# DMX.net
KiCad netlist of a schematic drawn in Altium Designer
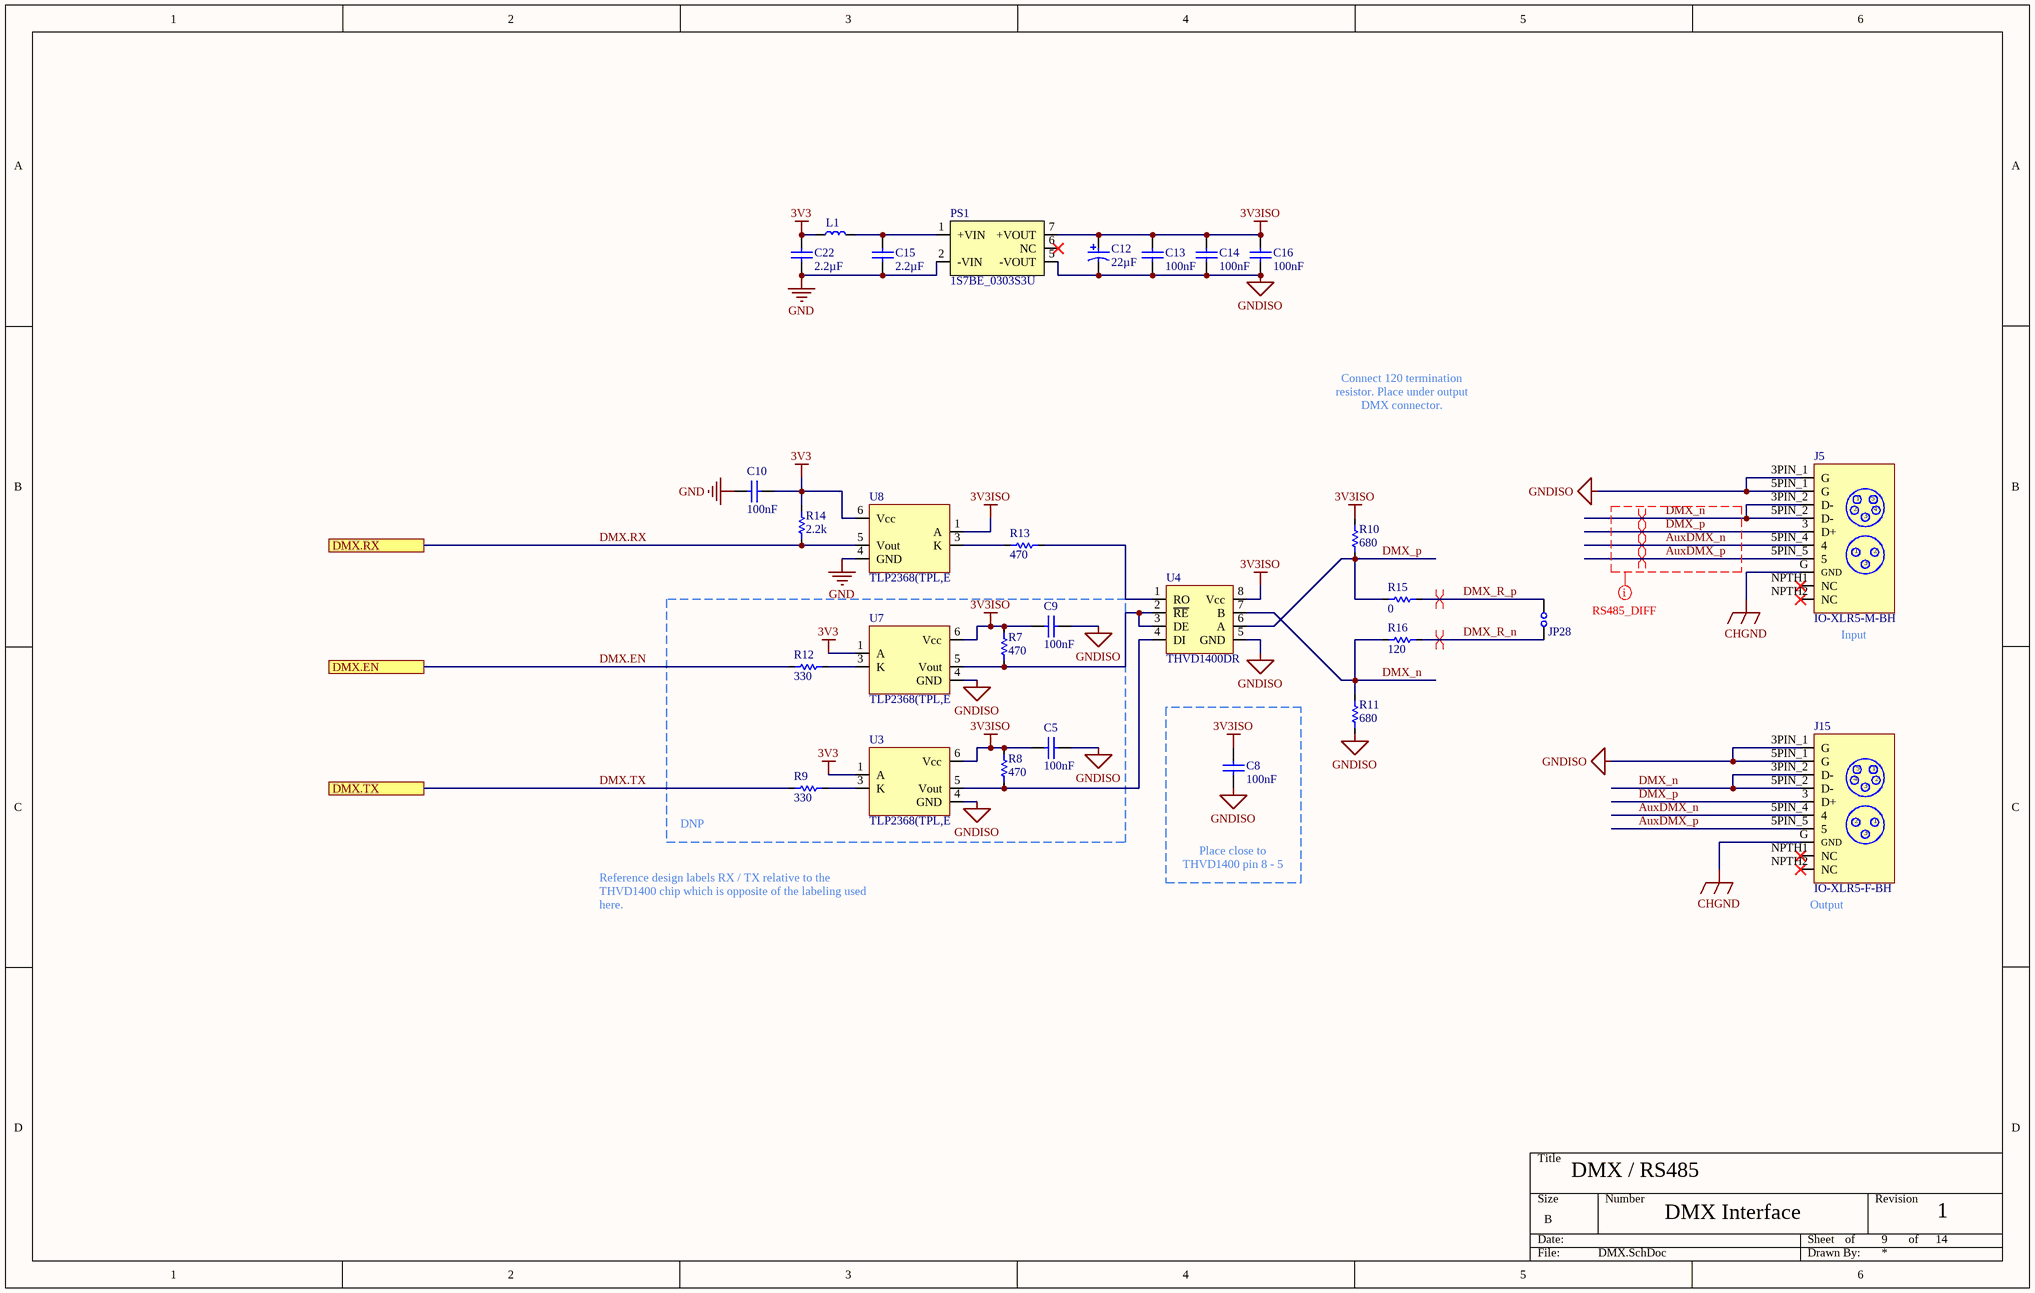
[diagram p0: DMX.SchDoc]

(export (version "E")
  (design (tool "Eeschema 10.0.6"))
  (components
    (comp (ref "C5")
      (value "100nF")
      (footprint "CAPC1608X10N_0603_MED")
      (fields (field (name "Comment") "CC0603KRX7R0BB104"))
      (libsource (lib "Equus Computer Systems") (part "CAP-NP-2"))
    )
    (comp (ref "C8")
      (value "100nF")
      (footprint "CAPC1608X10N_0603_MED")
      (fields (field (name "Comment") "CC0603KRX7R0BB104"))
      (libsource (lib "Equus Computer Systems") (part "CAP-NP-2"))
    )
    (comp (ref "C9")
      (value "100nF")
      (footprint "CAPC1608X10N_0603_MED")
      (fields (field (name "Comment") "CC0603KRX7R0BB104"))
      (libsource (lib "Equus Computer Systems") (part "CAP-NP-2"))
    )
    (comp (ref "C10")
      (value "100nF")
      (footprint "CAPC1608X10N_0603_MED")
      (fields (field (name "Comment") "CC0603KRX7R0BB104"))
      (libsource (lib "Equus Computer Systems") (part "CAP-NP-2"))
    )
    (comp (ref "C12")
      (value "22µF")
      (footprint "CAPCP3528X21N_1210_1411_MED")
      (fields (field (name "TOLERANCE") "10%") (field (name "Comment") "TPSB226K010R0500"))
      (libsource (lib "Equus Computer Systems") (part "CAP-P-2"))
    )
    (comp (ref "C13")
      (value "100nF")
      (footprint "CAPC1608X10N_0603_MED")
      (fields (field (name "Comment") "CC0603KRX7R0BB104"))
      (libsource (lib "Equus Computer Systems") (part "CAP-NP-2"))
    )
    (comp (ref "C14")
      (value "100nF")
      (footprint "CAPC1608X10N_0603_MED")
      (fields (field (name "Comment") "CC0603KRX7R0BB104"))
      (libsource (lib "Equus Computer Systems") (part "CAP-NP-2"))
    )
    (comp (ref "C15")
      (value "2.2µF")
      (footprint "CAPC2012X14N_0805_MED")
      (description "Ceramic Capacitor, Multilayer, Ceramic, 2.2uF, 50V, 10%, X6S, 0805")
      (fields (field (name "TOLERANCE") "10%") (field (name "Comment") "CGA4J3X7R1H225K125AE"))
      (libsource (lib "Equus Computer Systems") (part "CAP-NP-2"))
    )
    (comp (ref "C16")
      (value "100nF")
      (footprint "CAPC1608X10N_0603_MED")
      (fields (field (name "Comment") "CC0603KRX7R0BB104"))
      (libsource (lib "Equus Computer Systems") (part "CAP-NP-2"))
    )
    (comp (ref "C22")
      (value "2.2µF")
      (footprint "CAPC2012X14N_0805_MED")
      (description "Ceramic Capacitor, Multilayer, Ceramic, 2.2uF, 50V, 10%, X6S, 0805")
      (fields (field (name "TOLERANCE") "10%") (field (name "Comment") "CGA4J3X7R1H225K125AE"))
      (libsource (lib "Equus Computer Systems") (part "CAP-NP-2"))
    )
    (comp (ref "J5")
      (value "IO-XLR5-M-BH")
      (footprint "IO-XLR5-M-BH-Footprint-1")
      (description "B Series, 5 Pin XLR, Male, Horizontal Pcb Mount With Separate Ground Pin")
      (libsource (lib "Equus Computer Systems") (part "XLR5-M"))
    )
    (comp (ref "J15")
      (value "IO-XLR5-F-BH")
      (footprint "IO-XLR5-F-BH-Footprint-1")
      (description "B-Series 5-Pin XLR Female Horizontal PCB Mount with Separate Ground-Pin Metal Face Plate")
      (libsource (lib "Equus Computer Systems") (part "XLR5-F"))
    )
    (comp (ref "JP28")
      (value "Jumper 2 x 1 NO 0.1\" SMT")
      (footprint "Jumper 2 x 1 NO 0.1\" SMT-Footprint-1")
      (libsource (lib "Equus Computer Systems") (part "Jumper 2 NO"))
    )
    (comp (ref "L1")
      (value "SRR6038-180Y")
      (footprint "IND_SRR6038-180Y")
      (description "General Purpose Inductor, 18uH, 30%, 1 Element, Ferrite-Core, SMD, 2727")
      (fields (field (name "TOLERANCE") "30%"))
      (libsource (lib "Equus Computer Systems") (part "IND-2"))
    )
    (comp (ref "PS1")
      (value "1S7BE_0303S3U")
      (footprint "CONV_1S7BE_0303S3U")
      (description "ISOLATED MODULE DC DC CONVERTERS")
      (fields (field (name "MF") "Gaptec"))
      (libsource (lib "Equus Computer Systems") (part "1S7BE_0303S3U"))
    )
    (comp (ref "R7")
      (value "470")
      (footprint "RESC1608X06N_0603_MED")
      (fields
        (field (name "TOLERANCE") "1%")
        (field (name "POWER") "100mW")
        (field (name "Comment") "RC0603FR-07470RL")
      )
      (libsource (lib "Equus Computer Systems") (part "RES-2"))
    )
    (comp (ref "R8")
      (value "470")
      (footprint "RESC1608X06N_0603_MED")
      (fields
        (field (name "TOLERANCE") "1%")
        (field (name "POWER") "100mW")
        (field (name "Comment") "RC0603FR-07470RL")
      )
      (libsource (lib "Equus Computer Systems") (part "RES-2"))
    )
    (comp (ref "R9")
      (value "330")
      (footprint "RESC1608X06N_0603_MED")
      (fields
        (field (name "POWER") "100mW")
        (field (name "TOLERANCE") "1%")
        (field (name "Comment") "RC0603FR-07330RL")
      )
      (libsource (lib "Equus Computer Systems") (part "RES-2"))
    )
    (comp (ref "R10")
      (value "680")
      (footprint "RESC1608X06N_0603_MED")
      (fields
        (field (name "TOLERANCE") "1%")
        (field (name "POWER") "100mW")
        (field (name "Comment") "RC0603FR-07680RL")
      )
      (libsource (lib "Equus Computer Systems") (part "RES-2"))
    )
    (comp (ref "R11")
      (value "680")
      (footprint "RESC1608X06N_0603_MED")
      (fields
        (field (name "TOLERANCE") "1%")
        (field (name "POWER") "100mW")
        (field (name "Comment") "RC0603FR-07680RL")
      )
      (libsource (lib "Equus Computer Systems") (part "RES-2"))
    )
    (comp (ref "R12")
      (value "330")
      (footprint "RESC1608X06N_0603_MED")
      (fields
        (field (name "POWER") "100mW")
        (field (name "TOLERANCE") "1%")
        (field (name "Comment") "RC0603FR-07330RL")
      )
      (libsource (lib "Equus Computer Systems") (part "RES-2"))
    )
    (comp (ref "R13")
      (value "470")
      (footprint "RESC1608X06N_0603_MED")
      (fields
        (field (name "TOLERANCE") "1%")
        (field (name "POWER") "100mW")
        (field (name "Comment") "RC0603FR-07470RL")
      )
      (libsource (lib "Equus Computer Systems") (part "RES-2"))
    )
    (comp (ref "R14")
      (value "2.2k")
      (footprint "RESC1608X06N_0603_MED")
      (fields
        (field (name "TOLERANCE") "1%")
        (field (name "POWER") "100mW")
        (field (name "Comment") "RC0603FR-072K2L")
      )
      (libsource (lib "Equus Computer Systems") (part "RES-2"))
    )
    (comp (ref "R15")
      (value "0")
      (footprint "RESC1608X06N_0603_MED")
      (description "RC Series 0603 0.1 W 0 Ohm Jumper Surface Mount Thick Film Chip Resistor")
      (fields (field (name "POWER") "100mW") (field (name "TOLERANCE") "1%"))
      (libsource (lib "Equus Computer Systems") (part "RES-2"))
    )
    (comp (ref "R16")
      (value "120")
      (footprint "RESC1608X06N_0603_MED")
      (description "Res General Purpose Thick Film 0603 120 Ohm 1% 1/10W ±100ppm/°C Molded SMD Paper T/R")
      (fields (field (name "POWER") "100mW") (field (name "TOLERANCE") "1%"))
      (libsource (lib "Equus Computer Systems") (part "RES-2"))
    )
    (comp (ref "U3")
      (value "TLP2368(TPL,E")
      (footprint "SOT125P700X220-5N")
      (description "Logic IC Output Optocoupler, 1-Channel, 1-Element, 3750V Isolation, 20MBps")
      (libsource (lib "Equus Computer Systems") (part "TLP2368-Symbol-1"))
    )
    (comp (ref "U4")
      (value "THVD1400DR")
      (footprint "SOIC127P600X175-8N")
      (description "Line Transceiver, 1 Func, 1 Driver, 1 Rcvr, PDSO8")
      (libsource (lib "Equus Computer Systems") (part "THVD1400DR"))
    )
    (comp (ref "U7")
      (value "TLP2368(TPL,E")
      (footprint "SOT125P700X220-5N")
      (description "Logic IC Output Optocoupler, 1-Channel, 1-Element, 3750V Isolation, 20MBps")
      (libsource (lib "Equus Computer Systems") (part "TLP2368-Symbol-1"))
    )
    (comp (ref "U8")
      (value "TLP2368(TPL,E")
      (footprint "SOT125P700X220-5N")
      (description "Logic IC Output Optocoupler, 1-Channel, 1-Element, 3750V Isolation, 20MBps")
      (libsource (lib "") (part "TLP2368-Symbol-1_1"))
    )
  )
  (nets
    (net (code "1") (name "/AuxDMX_n") (class "Default")
      (node (ref "J15") (pin "5PIN_4") (pinfunction "4_5PIN_4") (pintype "passive"))
      (node (ref "J5") (pin "5PIN_4") (pinfunction "4_5PIN_4") (pintype "passive"))
    )
    (net (code "2") (name "/AuxDMX_p") (class "Default")
      (node (ref "J15") (pin "5PIN_5") (pinfunction "5_5PIN_5") (pintype "passive"))
      (node (ref "J5") (pin "5PIN_5") (pinfunction "5_5PIN_5") (pintype "passive"))
    )
    (net (code "3") (name "/DMX.EN") (class "Default")
      (node (ref "R12") (pin "1") (pinfunction "1_1") (pintype "passive"))
    )
    (net (code "4") (name "/DMX.RX") (class "Default")
      (node (ref "R14") (pin "1") (pinfunction "1_1") (pintype "passive"))
      (node (ref "U8") (pin "5") (pinfunction "Vout_5") (pintype "passive"))
    )
    (net (code "5") (name "/DMX.TX") (class "Default")
      (node (ref "R9") (pin "1") (pinfunction "1_1") (pintype "passive"))
    )
    (net (code "6") (name "/DMX_R_n") (class "Default")
      (node (ref "JP28") (pin "2") (pinfunction "2_2") (pintype "passive"))
      (node (ref "R16") (pin "2") (pinfunction "2_2") (pintype "passive"))
    )
    (net (code "7") (name "/DMX_R_p") (class "Default")
      (node (ref "JP28") (pin "1") (pinfunction "1_1") (pintype "passive"))
      (node (ref "R15") (pin "2") (pinfunction "2_2") (pintype "passive"))
    )
    (net (code "8") (name "/DMX_n") (class "Default")
      (node (ref "J15") (pin "3PIN_2") (pinfunction "D-_3PIN_2") (pintype "passive"))
      (node (ref "J15") (pin "5PIN_2") (pinfunction "D-_5PIN_2") (pintype "passive"))
      (node (ref "J5") (pin "3PIN_2") (pinfunction "D-_3PIN_2") (pintype "passive"))
      (node (ref "J5") (pin "5PIN_2") (pinfunction "D-_5PIN_2") (pintype "passive"))
      (node (ref "R11") (pin "2") (pinfunction "2_2") (pintype "passive"))
      (node (ref "R16") (pin "1") (pinfunction "1_1") (pintype "passive"))
      (node (ref "U4") (pin "7") (pinfunction "B_7") (pintype "passive"))
    )
    (net (code "9") (name "/DMX_p") (class "Default")
      (node (ref "J15") (pin "3") (pinfunction "D+_3") (pintype "passive"))
      (node (ref "J5") (pin "3") (pinfunction "D+_3") (pintype "passive"))
      (node (ref "R10") (pin "1") (pinfunction "1_1") (pintype "passive"))
      (node (ref "R15") (pin "1") (pinfunction "1_1") (pintype "passive"))
      (node (ref "U4") (pin "6") (pinfunction "A_6") (pintype "passive"))
    )
    (net (code "10") (name "3V3") (class "Default")
      (node (ref "C10") (pin "1") (pinfunction "1_1") (pintype "passive"))
      (node (ref "C22") (pin "2") (pinfunction "2_2") (pintype "passive"))
      (node (ref "L1") (pin "1") (pinfunction "1_1") (pintype "passive"))
      (node (ref "R14") (pin "2") (pinfunction "2_2") (pintype "passive"))
      (node (ref "U3") (pin "1") (pinfunction "A_1") (pintype "passive"))
      (node (ref "U7") (pin "1") (pinfunction "A_1") (pintype "passive"))
      (node (ref "U8") (pin "6") (pinfunction "Vcc_6") (pintype "passive"))
    )
    (net (code "11") (name "3V3ISO") (class "Default")
      (node (ref "C12") (pin "1") (pinfunction "1_1") (pintype "passive"))
      (node (ref "C13") (pin "2") (pinfunction "2_2") (pintype "passive"))
      (node (ref "C14") (pin "2") (pinfunction "2_2") (pintype "passive"))
      (node (ref "C16") (pin "2") (pinfunction "2_2") (pintype "passive"))
      (node (ref "C5") (pin "2") (pinfunction "2_2") (pintype "passive"))
      (node (ref "C8") (pin "1") (pinfunction "1_1") (pintype "passive"))
      (node (ref "C9") (pin "2") (pinfunction "2_2") (pintype "passive"))
      (node (ref "PS1") (pin "7") (pinfunction "+VOUT_7") (pintype "passive"))
      (node (ref "R10") (pin "2") (pinfunction "2_2") (pintype "passive"))
      (node (ref "R7") (pin "2") (pinfunction "2_2") (pintype "passive"))
      (node (ref "R8") (pin "2") (pinfunction "2_2") (pintype "passive"))
      (node (ref "U3") (pin "6") (pinfunction "Vcc_6") (pintype "passive"))
      (node (ref "U4") (pin "8") (pinfunction "Vcc_8") (pintype "passive"))
      (node (ref "U7") (pin "6") (pinfunction "Vcc_6") (pintype "passive"))
      (node (ref "U8") (pin "1") (pinfunction "A_1") (pintype "passive"))
    )
    (net (code "12") (name "CHGND") (class "Default")
      (node (ref "J15") (pin "G") (pinfunction "GND_G") (pintype "passive"))
      (node (ref "J5") (pin "G") (pinfunction "GND_G") (pintype "passive"))
    )
    (net (code "13") (name "GND") (class "Default")
      (node (ref "C10") (pin "2") (pinfunction "2_2") (pintype "passive"))
      (node (ref "C15") (pin "1") (pinfunction "1_1") (pintype "passive"))
      (node (ref "C22") (pin "1") (pinfunction "1_1") (pintype "passive"))
      (node (ref "PS1") (pin "2") (pinfunction "-VIN_2") (pintype "passive"))
      (node (ref "U8") (pin "4") (pinfunction "GND_4") (pintype "passive"))
    )
    (net (code "14") (name "GNDISO") (class "Default")
      (node (ref "C12") (pin "2") (pinfunction "2_2") (pintype "passive"))
      (node (ref "C13") (pin "1") (pinfunction "1_1") (pintype "passive"))
      (node (ref "C14") (pin "1") (pinfunction "1_1") (pintype "passive"))
      (node (ref "C16") (pin "1") (pinfunction "1_1") (pintype "passive"))
      (node (ref "C5") (pin "1") (pinfunction "1_1") (pintype "passive"))
      (node (ref "C8") (pin "2") (pinfunction "2_2") (pintype "passive"))
      (node (ref "C9") (pin "1") (pinfunction "1_1") (pintype "passive"))
      (node (ref "J15") (pin "3PIN_1") (pinfunction "G_3PIN_1") (pintype "passive"))
      (node (ref "J15") (pin "5PIN_1") (pinfunction "G_5PIN_1") (pintype "passive"))
      (node (ref "J5") (pin "3PIN_1") (pinfunction "G_3PIN_1") (pintype "passive"))
      (node (ref "J5") (pin "5PIN_1") (pinfunction "G_5PIN_1") (pintype "passive"))
      (node (ref "PS1") (pin "5") (pinfunction "-VOUT_5") (pintype "passive"))
      (node (ref "R11") (pin "1") (pinfunction "1_1") (pintype "passive"))
      (node (ref "U3") (pin "4") (pinfunction "GND_4") (pintype "passive"))
      (node (ref "U4") (pin "5") (pinfunction "GND_5") (pintype "passive"))
      (node (ref "U7") (pin "4") (pinfunction "GND_4") (pintype "passive"))
    )
    (net (code "15") (name "Net-(PS1-+VIN)") (class "Default")
      (node (ref "C15") (pin "2") (pinfunction "2_2") (pintype "passive"))
      (node (ref "L1") (pin "2") (pinfunction "2_2") (pintype "passive"))
      (node (ref "PS1") (pin "1") (pinfunction "+VIN_1") (pintype "passive"))
    )
    (net (code "16") (name "Net-(U3-K)") (class "Default")
      (node (ref "R9") (pin "2") (pinfunction "2_2") (pintype "passive"))
      (node (ref "U3") (pin "3") (pinfunction "K_3") (pintype "passive"))
    )
    (net (code "17") (name "Net-(U3-Vout)") (class "Default")
      (node (ref "R8") (pin "1") (pinfunction "1_1") (pintype "passive"))
      (node (ref "U3") (pin "5") (pinfunction "Vout_5") (pintype "passive"))
      (node (ref "U4") (pin "4") (pinfunction "DI_4") (pintype "passive"))
    )
    (net (code "18") (name "Net-(U4-DE)") (class "Default")
      (node (ref "R7") (pin "1") (pinfunction "1_1") (pintype "passive"))
      (node (ref "U4") (pin "2") (pinfunction "~{RE}_2") (pintype "passive"))
      (node (ref "U4") (pin "3") (pinfunction "DE_3") (pintype "passive"))
      (node (ref "U7") (pin "5") (pinfunction "Vout_5") (pintype "passive"))
    )
    (net (code "19") (name "Net-(U4-RO)") (class "Default")
      (node (ref "R13") (pin "2") (pinfunction "2_2") (pintype "passive"))
      (node (ref "U4") (pin "1") (pinfunction "RO_1") (pintype "passive"))
    )
    (net (code "20") (name "Net-(U7-K)") (class "Default")
      (node (ref "R12") (pin "2") (pinfunction "2_2") (pintype "passive"))
      (node (ref "U7") (pin "3") (pinfunction "K_3") (pintype "passive"))
    )
    (net (code "21") (name "Net-(U8-K)") (class "Default")
      (node (ref "R13") (pin "1") (pinfunction "1_1") (pintype "passive"))
      (node (ref "U8") (pin "3") (pinfunction "K_3") (pintype "passive"))
    )
    (net (code "22") (name "unconnected-(J5-NC-PadNPTH1)") (class "Default")
      (node (ref "J5") (pin "NPTH1") (pinfunction "NC_NPTH1") (pintype "passive+no_connect"))
    )
    (net (code "23") (name "unconnected-(J5-NC-PadNPTH2)") (class "Default")
      (node (ref "J5") (pin "NPTH2") (pinfunction "NC_NPTH2") (pintype "passive+no_connect"))
    )
    (net (code "24") (name "unconnected-(J15-NC-PadNPTH1)") (class "Default")
      (node (ref "J15") (pin "NPTH1") (pinfunction "NC_NPTH1") (pintype "passive+no_connect"))
    )
    (net (code "25") (name "unconnected-(J15-NC-PadNPTH2)") (class "Default")
      (node (ref "J15") (pin "NPTH2") (pinfunction "NC_NPTH2") (pintype "passive+no_connect"))
    )
    (net (code "26") (name "unconnected-(PS1-NC-Pad6)") (class "Default")
      (node (ref "PS1") (pin "6") (pinfunction "NC_6") (pintype "passive+no_connect"))
    )
  )
)
